# Sheet1.net
KiCad netlist of a schematic drawn in Altium Designer
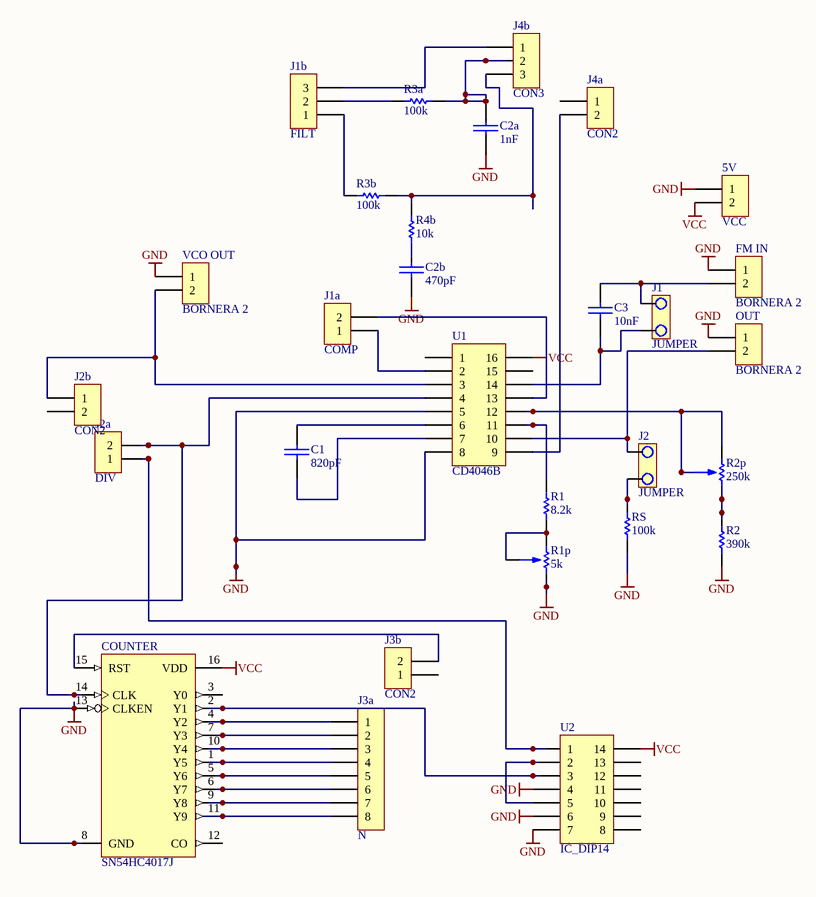
[diagram p0: Sheet1.SchDoc]

(export (version "E")
  (design (tool "Eeschema 10.0.6"))
  (components
    (comp (ref "5V") (value "VCC") (footprint "BORNERA2") (libsource (lib "LIBEBAL") (part "BORNERA 2")))
    (comp (ref "C1") (value "820pF") (footprint "CAP200") (libsource (lib "LIBEBAL") (part "CAP")))
    (comp (ref "C2a") (value "1nF") (footprint "CAP200") (libsource (lib "LIBEBAL") (part "CAP")))
    (comp (ref "C2b") (value "470pF") (footprint "CAP200") (libsource (lib "LIBEBAL") (part "CAP")))
    (comp (ref "C3") (value "10nF") (footprint "CAP200") (libsource (lib "LIBEBAL") (part "CAP")))
    (comp (ref "COUNTER")
      (value "SN54HC4017J")
      (footprint "J016")
      (description "Decade Counter / Divider")
      (fields (field (name "PUBLISHER") "Altium Limited"))
      (libsource (lib "TI Logic Counter") (part "SN54HC4017J"))
    )
    (comp (ref "FM IN")
      (value "BORNERA 2")
      (footprint "BORNERA2")
      (libsource (lib "LIBEBAL") (part "BORNERA 2"))
    )
    (comp (ref "J1") (value "JUMPER") (footprint "JUMPER2") (libsource (lib "LIBEBAL") (part "JUMPER")))
    (comp (ref "J1a") (value "COMP") (footprint "SIP2") (libsource (lib "") (part "CON2_1")))
    (comp (ref "J1b") (value "FILT") (footprint "SIP3") (libsource (lib "") (part "CON3_1")))
    (comp (ref "J2") (value "JUMPER") (footprint "JUMPER2") (libsource (lib "LIBEBAL") (part "JUMPER")))
    (comp (ref "J2a") (value "DIV") (footprint "SIP2") (libsource (lib "") (part "CON2_1")))
    (comp (ref "J2b") (value "CON2") (footprint "SIP2") (libsource (lib "LIBEBAL") (part "CON2")))
    (comp (ref "J3a") (value "N") (footprint "SIP8") (libsource (lib "LIBEBAL") (part "CON8")))
    (comp (ref "J3b") (value "CON2") (footprint "SIP2") (libsource (lib "") (part "CON2_1")))
    (comp (ref "J4a") (value "CON2") (footprint "SIP2") (libsource (lib "LIBEBAL") (part "CON2")))
    (comp (ref "J4b") (value "CON3") (footprint "SIP3") (libsource (lib "LIBEBAL") (part "CON3")))
    (comp (ref "OUT")
      (value "BORNERA 2")
      (footprint "BORNERA2")
      (libsource (lib "LIBEBAL") (part "BORNERA 2"))
    )
    (comp (ref "R1") (value "8.2k") (footprint "RES300") (libsource (lib "LIBEBAL") (part "RES")))
    (comp (ref "R1p") (value "5k") (footprint "PRESET V") (libsource (lib "LIBEBAL") (part "PRESET")))
    (comp (ref "R2") (value "390k") (footprint "RES300") (libsource (lib "LIBEBAL") (part "RES")))
    (comp (ref "R2p") (value "250k") (footprint "PRESET V") (libsource (lib "LIBEBAL") (part "PRESET")))
    (comp (ref "R3a") (value "100k") (footprint "RES300") (libsource (lib "LIBEBAL") (part "RES")))
    (comp (ref "R3b") (value "100k") (footprint "RES300") (libsource (lib "LIBEBAL") (part "RES")))
    (comp (ref "R4b") (value "10k") (footprint "RES300") (libsource (lib "LIBEBAL") (part "RES")))
    (comp (ref "RS") (value "100k") (footprint "RES300") (libsource (lib "LIBEBAL") (part "RES")))
    (comp (ref "U1") (value "CD4046B") (footprint "DIP16") (libsource (lib "LIBEBAL") (part "IC_DIP16")))
    (comp (ref "U2") (value "IC_DIP14") (footprint "DIP14") (libsource (lib "LIBEBAL") (part "IC_DIP14")))
    (comp (ref "VCO OUT")
      (value "BORNERA 2")
      (footprint "BORNERA2")
      (libsource (lib "LIBEBAL") (part "BORNERA 2"))
    )
  )
  (nets
    (net (code "1") (name "GND") (class "Default")
      (node (ref "5V") (pin "1") (pinfunction "1_1") (pintype "passive"))
      (node (ref "C2a") (pin "2") (pinfunction "2_2") (pintype "passive"))
      (node (ref "C2b") (pin "2") (pinfunction "2_2") (pintype "passive"))
      (node (ref "COUNTER") (pin "13") (pinfunction "CLKEN_13") (pintype "input"))
      (node (ref "COUNTER") (pin "8") (pinfunction "GND_8") (pintype "power_in"))
      (node (ref "FM IN") (pin "1") (pinfunction "1_1") (pintype "passive"))
      (node (ref "OUT") (pin "1") (pinfunction "1_1") (pintype "passive"))
      (node (ref "R1p") (pin "1") (pinfunction "1_1") (pintype "passive"))
      (node (ref "R2") (pin "1") (pinfunction "1_1") (pintype "passive"))
      (node (ref "RS") (pin "1") (pinfunction "1_1") (pintype "passive"))
      (node (ref "U1") (pin "5") (pinfunction "5_5") (pintype "passive"))
      (node (ref "U1") (pin "8") (pinfunction "8_8") (pintype "passive"))
      (node (ref "U2") (pin "4") (pinfunction "4_4") (pintype "passive"))
      (node (ref "U2") (pin "6") (pinfunction "6_6") (pintype "passive"))
      (node (ref "U2") (pin "7") (pinfunction "7_7") (pintype "passive"))
      (node (ref "VCO OUT") (pin "1") (pinfunction "1_1") (pintype "passive"))
    )
    (net (code "2") (name "Net-(C1-Pad1)") (class "Default")
      (node (ref "C1") (pin "1") (pinfunction "1_1") (pintype "passive"))
      (node (ref "U1") (pin "6") (pinfunction "6_6") (pintype "passive"))
    )
    (net (code "3") (name "Net-(C1-Pad2)") (class "Default")
      (node (ref "C1") (pin "2") (pinfunction "2_2") (pintype "passive"))
      (node (ref "U1") (pin "7") (pinfunction "7_7") (pintype "passive"))
    )
    (net (code "4") (name "Net-(C2a-Pad1)") (class "Default")
      (node (ref "C2a") (pin "1") (pinfunction "1_1") (pintype "passive"))
      (node (ref "J4b") (pin "2") (pinfunction "2_2") (pintype "passive"))
      (node (ref "R3a") (pin "2") (pinfunction "2_2") (pintype "passive"))
    )
    (net (code "5") (name "Net-(C2b-Pad1)") (class "Default")
      (node (ref "C2b") (pin "1") (pinfunction "1_1") (pintype "passive"))
      (node (ref "R4b") (pin "1") (pinfunction "1_1") (pintype "passive"))
    )
    (net (code "6") (name "Net-(C3-Pad1)") (class "Default")
      (node (ref "C3") (pin "1") (pinfunction "1_1") (pintype "passive"))
      (node (ref "FM IN") (pin "2") (pinfunction "2_2") (pintype "passive"))
      (node (ref "J1") (pin "2") (pinfunction "2_2") (pintype "passive"))
    )
    (net (code "7") (name "Net-(C3-Pad2)") (class "Default")
      (node (ref "C3") (pin "2") (pinfunction "2_2") (pintype "passive"))
      (node (ref "J1") (pin "1") (pinfunction "1_1") (pintype "passive"))
      (node (ref "U1") (pin "14") (pinfunction "14_14") (pintype "passive"))
    )
    (net (code "8") (name "Net-(COUNTER-CLK)") (class "Default")
      (node (ref "COUNTER") (pin "14") (pinfunction "CLK_14") (pintype "input"))
      (node (ref "J2a") (pin "2") (pinfunction "2_2") (pintype "passive"))
      (node (ref "U1") (pin "4") (pinfunction "4_4") (pintype "passive"))
    )
    (net (code "9") (name "Net-(COUNTER-RST)") (class "Default")
      (node (ref "COUNTER") (pin "15") (pinfunction "RST_15") (pintype "input"))
      (node (ref "J3b") (pin "2") (pinfunction "2_2") (pintype "passive"))
    )
    (net (code "10") (name "Net-(COUNTER-Y1)") (class "Default")
      (node (ref "COUNTER") (pin "2") (pinfunction "Y1_2") (pintype "output"))
      (node (ref "U2") (pin "3") (pinfunction "3_3") (pintype "passive"))
    )
    (net (code "11") (name "Net-(COUNTER-Y2)") (class "Default")
      (node (ref "COUNTER") (pin "4") (pinfunction "Y2_4") (pintype "output"))
      (node (ref "J3a") (pin "1") (pinfunction "1_1") (pintype "passive"))
    )
    (net (code "12") (name "Net-(COUNTER-Y3)") (class "Default")
      (node (ref "COUNTER") (pin "7") (pinfunction "Y3_7") (pintype "output"))
      (node (ref "J3a") (pin "2") (pinfunction "2_2") (pintype "passive"))
    )
    (net (code "13") (name "Net-(COUNTER-Y4)") (class "Default")
      (node (ref "COUNTER") (pin "10") (pinfunction "Y4_10") (pintype "output"))
      (node (ref "J3a") (pin "3") (pinfunction "3_3") (pintype "passive"))
    )
    (net (code "14") (name "Net-(COUNTER-Y5)") (class "Default")
      (node (ref "COUNTER") (pin "1") (pinfunction "Y5_1") (pintype "output"))
      (node (ref "J3a") (pin "4") (pinfunction "4_4") (pintype "passive"))
    )
    (net (code "15") (name "Net-(COUNTER-Y6)") (class "Default")
      (node (ref "COUNTER") (pin "5") (pinfunction "Y6_5") (pintype "output"))
      (node (ref "J3a") (pin "5") (pinfunction "5_5") (pintype "passive"))
    )
    (net (code "16") (name "Net-(COUNTER-Y7)") (class "Default")
      (node (ref "COUNTER") (pin "6") (pinfunction "Y7_6") (pintype "output"))
      (node (ref "J3a") (pin "6") (pinfunction "6_6") (pintype "passive"))
    )
    (net (code "17") (name "Net-(COUNTER-Y8)") (class "Default")
      (node (ref "COUNTER") (pin "9") (pinfunction "Y8_9") (pintype "output"))
      (node (ref "J3a") (pin "7") (pinfunction "7_7") (pintype "passive"))
    )
    (net (code "18") (name "Net-(COUNTER-Y9)") (class "Default")
      (node (ref "COUNTER") (pin "11") (pinfunction "Y9_11") (pintype "output"))
      (node (ref "J3a") (pin "8") (pinfunction "8_8") (pintype "passive"))
    )
    (net (code "19") (name "Net-(J1a-Pad1)") (class "Default")
      (node (ref "J1a") (pin "1") (pinfunction "1_1") (pintype "passive"))
      (node (ref "U1") (pin "2") (pinfunction "2_2") (pintype "passive"))
    )
    (net (code "20") (name "Net-(J1a-Pad2)") (class "Default")
      (node (ref "J1a") (pin "2") (pinfunction "2_2") (pintype "passive"))
      (node (ref "U1") (pin "13") (pinfunction "13_13") (pintype "passive"))
    )
    (net (code "21") (name "Net-(J1b-Pad1)") (class "Default")
      (node (ref "J1b") (pin "1") (pinfunction "1_1") (pintype "passive"))
      (node (ref "R3b") (pin "1") (pinfunction "1_1") (pintype "passive"))
    )
    (net (code "22") (name "Net-(J1b-Pad2)") (class "Default")
      (node (ref "J1b") (pin "2") (pinfunction "2_2") (pintype "passive"))
      (node (ref "R3a") (pin "1") (pinfunction "1_1") (pintype "passive"))
    )
    (net (code "23") (name "Net-(J1b-Pad3)") (class "Default")
      (node (ref "J1b") (pin "3") (pinfunction "3_3") (pintype "passive"))
      (node (ref "J4b") (pin "1") (pinfunction "1_1") (pintype "passive"))
    )
    (net (code "24") (name "Net-(J2-Pad1)") (class "Default")
      (node (ref "J2") (pin "1") (pinfunction "1_1") (pintype "passive"))
      (node (ref "RS") (pin "2") (pinfunction "2_2") (pintype "passive"))
    )
    (net (code "25") (name "Net-(J2-Pad2)") (class "Default")
      (node (ref "J2") (pin "2") (pinfunction "2_2") (pintype "passive"))
      (node (ref "OUT") (pin "2") (pinfunction "2_2") (pintype "passive"))
      (node (ref "U1") (pin "10") (pinfunction "10_10") (pintype "passive"))
    )
    (net (code "26") (name "Net-(J2a-Pad1)") (class "Default")
      (node (ref "J2a") (pin "1") (pinfunction "1_1") (pintype "passive"))
      (node (ref "U2") (pin "1") (pinfunction "1_1") (pintype "passive"))
    )
    (net (code "27") (name "Net-(J2b-Pad1)") (class "Default")
      (node (ref "J2b") (pin "1") (pinfunction "1_1") (pintype "passive"))
      (node (ref "U1") (pin "3") (pinfunction "3_3") (pintype "passive"))
      (node (ref "VCO OUT") (pin "2") (pinfunction "2_2") (pintype "passive"))
    )
    (net (code "28") (name "Net-(J4a-Pad2)") (class "Default")
      (node (ref "J4a") (pin "2") (pinfunction "2_2") (pintype "passive"))
      (node (ref "U1") (pin "9") (pinfunction "9_9") (pintype "passive"))
    )
    (net (code "29") (name "Net-(J4b-Pad3)") (class "Default")
      (node (ref "J4b") (pin "3") (pinfunction "3_3") (pintype "passive"))
      (node (ref "R3b") (pin "2") (pinfunction "2_2") (pintype "passive"))
      (node (ref "R4b") (pin "2") (pinfunction "2_2") (pintype "passive"))
    )
    (net (code "30") (name "Net-(R1-Pad1)") (class "Default")
      (node (ref "R1") (pin "1") (pinfunction "1_1") (pintype "passive"))
      (node (ref "R1p") (pin "2") (pinfunction "2_2") (pintype "passive"))
      (node (ref "R1p") (pin "3") (pinfunction "3_3") (pintype "passive"))
    )
    (net (code "31") (name "Net-(R1-Pad2)") (class "Default")
      (node (ref "R1") (pin "2") (pinfunction "2_2") (pintype "passive"))
      (node (ref "U1") (pin "11") (pinfunction "11_11") (pintype "passive"))
    )
    (net (code "32") (name "Net-(R2-Pad2)") (class "Default")
      (node (ref "R2") (pin "2") (pinfunction "2_2") (pintype "passive"))
      (node (ref "R2p") (pin "1") (pinfunction "1_1") (pintype "passive"))
    )
    (net (code "33") (name "Net-(R2p-Pad2)") (class "Default")
      (node (ref "R2p") (pin "2") (pinfunction "2_2") (pintype "passive"))
      (node (ref "R2p") (pin "3") (pinfunction "3_3") (pintype "passive"))
      (node (ref "U1") (pin "12") (pinfunction "12_12") (pintype "passive"))
    )
    (net (code "34") (name "Net-(U2-Pad2)") (class "Default")
      (node (ref "U2") (pin "2") (pinfunction "2_2") (pintype "passive"))
      (node (ref "U2") (pin "5") (pinfunction "5_5") (pintype "passive"))
    )
    (net (code "35") (name "VCC") (class "Default")
      (node (ref "5V") (pin "2") (pinfunction "2_2") (pintype "passive"))
      (node (ref "COUNTER") (pin "16") (pinfunction "VDD_16") (pintype "power_in"))
      (node (ref "U1") (pin "16") (pinfunction "16_16") (pintype "passive"))
      (node (ref "U2") (pin "14") (pinfunction "14_14") (pintype "passive"))
    )
    (net (code "36") (name "unconnected-(COUNTER-CO-Pad12)") (class "Default")
      (node (ref "COUNTER") (pin "12") (pinfunction "CO_12") (pintype "output"))
    )
    (net (code "37") (name "unconnected-(COUNTER-Y0-Pad3)") (class "Default")
      (node (ref "COUNTER") (pin "3") (pinfunction "Y0_3") (pintype "output"))
    )
    (net (code "38") (name "unconnected-(J2b-Pad2)") (class "Default")
      (node (ref "J2b") (pin "2") (pinfunction "2_2") (pintype "passive"))
    )
    (net (code "39") (name "unconnected-(J3b-Pad1)") (class "Default")
      (node (ref "J3b") (pin "1") (pinfunction "1_1") (pintype "passive"))
    )
    (net (code "40") (name "unconnected-(J4a-Pad1)") (class "Default")
      (node (ref "J4a") (pin "1") (pinfunction "1_1") (pintype "passive"))
    )
    (net (code "41") (name "unconnected-(U1-Pad1)") (class "Default")
      (node (ref "U1") (pin "1") (pinfunction "1_1") (pintype "passive"))
    )
    (net (code "42") (name "unconnected-(U1-Pad15)") (class "Default")
      (node (ref "U1") (pin "15") (pinfunction "15_15") (pintype "passive"))
    )
    (net (code "43") (name "unconnected-(U2-Pad8)") (class "Default")
      (node (ref "U2") (pin "8") (pinfunction "8_8") (pintype "passive"))
    )
    (net (code "44") (name "unconnected-(U2-Pad9)") (class "Default")
      (node (ref "U2") (pin "9") (pinfunction "9_9") (pintype "passive"))
    )
    (net (code "45") (name "unconnected-(U2-Pad10)") (class "Default")
      (node (ref "U2") (pin "10") (pinfunction "10_10") (pintype "passive"))
    )
    (net (code "46") (name "unconnected-(U2-Pad11)") (class "Default")
      (node (ref "U2") (pin "11") (pinfunction "11_11") (pintype "passive"))
    )
    (net (code "47") (name "unconnected-(U2-Pad12)") (class "Default")
      (node (ref "U2") (pin "12") (pinfunction "12_12") (pintype "passive"))
    )
    (net (code "48") (name "unconnected-(U2-Pad13)") (class "Default")
      (node (ref "U2") (pin "13") (pinfunction "13_13") (pintype "passive"))
    )
  )
)
